# keychainlight.net
KiCad netlist of a schematic drawn in EAGLE
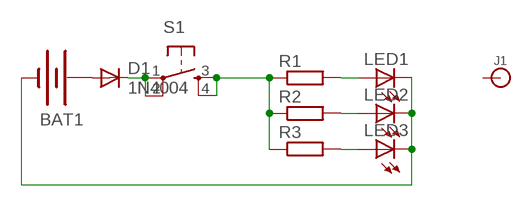
[diagram p0: schematic, sheet 1]

(export (version "E")
  (design (tool "Eeschema 10.0.6"))
  (components
    (comp (ref "BAT1")
      (value "BATTERY20PTH")
      (footprint "eagle-import:BATTCOM_20MM_PTH")
      (libsource (lib "eagle-import") (part "BATTERY20PTH"))
    )
    (comp (ref "D1")
      (value "1N4004")
      (footprint "eagle-import:DO41-10")
      (libsource (lib "eagle-import") (part "1N4004"))
    )
    (comp (ref "J1")
      (value "BANANA_CONN")
      (footprint "eagle-import:BANANA_CONN")
      (libsource (lib "eagle-import") (part "BANANA_CONN"))
    )
    (comp (ref "LED1")
      (value "LED5MM")
      (footprint "eagle-import:LED5MM")
      (libsource (lib "eagle-import") (part "LED5MM"))
    )
    (comp (ref "LED2")
      (value "LED5MM")
      (footprint "eagle-import:LED5MM")
      (libsource (lib "eagle-import") (part "LED5MM"))
    )
    (comp (ref "LED3")
      (value "LED5MM")
      (footprint "eagle-import:LED5MM")
      (libsource (lib "eagle-import") (part "LED5MM"))
    )
    (comp (ref "R1")
      (value "R-EU_0207/7")
      (footprint "eagle-import:0207_7")
      (libsource (lib "eagle-import") (part "R-EU_0207/7"))
    )
    (comp (ref "R2")
      (value "R-EU_0207/7")
      (footprint "eagle-import:0207_7")
      (libsource (lib "eagle-import") (part "R-EU_0207/7"))
    )
    (comp (ref "R3")
      (value "R-EU_0207/7")
      (footprint "eagle-import:0207_7")
      (libsource (lib "eagle-import") (part "R-EU_0207/7"))
    )
    (comp (ref "S1")
      (value "TAC_SWITCHPTH")
      (footprint "eagle-import:TACTILE-PTH")
      (libsource (lib "eagle-import") (part "TAC_SWITCHPTH"))
    )
  )
  (nets
    (net (code "1") (name "Net-(BAT1-+)") (class "Default")
      (node (ref "BAT1") (pin "1") (pinfunction "+_1") (pintype "power_in"))
      (node (ref "D1") (pin "A") (pinfunction "A_A") (pintype "passive"))
    )
    (net (code "2") (name "Net-(BAT1--)") (class "Default")
      (node (ref "BAT1") (pin "2") (pinfunction "-_2") (pintype "power_in"))
      (node (ref "LED1") (pin "K") (pinfunction "C_K") (pintype "passive"))
      (node (ref "LED2") (pin "K") (pinfunction "C_K") (pintype "passive"))
      (node (ref "LED3") (pin "K") (pinfunction "C_K") (pintype "passive"))
    )
    (net (code "3") (name "Net-(D1-PadC)") (class "Default")
      (node (ref "D1") (pin "C") (pinfunction "C_C") (pintype "passive"))
      (node (ref "S1") (pin "1") (pinfunction "1_1") (pintype "passive"))
      (node (ref "S1") (pin "2") (pinfunction "2_2") (pintype "passive"))
    )
    (net (code "4") (name "Net-(LED1-PadA)") (class "Default")
      (node (ref "LED1") (pin "A") (pinfunction "A_A") (pintype "passive"))
      (node (ref "R1") (pin "2") (pinfunction "2_2") (pintype "passive"))
    )
    (net (code "5") (name "Net-(LED2-PadA)") (class "Default")
      (node (ref "LED2") (pin "A") (pinfunction "A_A") (pintype "passive"))
      (node (ref "R2") (pin "2") (pinfunction "2_2") (pintype "passive"))
    )
    (net (code "6") (name "Net-(LED3-PadA)") (class "Default")
      (node (ref "LED3") (pin "A") (pinfunction "A_A") (pintype "passive"))
      (node (ref "R3") (pin "2") (pinfunction "2_2") (pintype "passive"))
    )
    (net (code "7") (name "Net-(R1-Pad1)") (class "Default")
      (node (ref "R1") (pin "1") (pinfunction "1_1") (pintype "passive"))
      (node (ref "R2") (pin "1") (pinfunction "1_1") (pintype "passive"))
      (node (ref "R3") (pin "1") (pinfunction "1_1") (pintype "passive"))
      (node (ref "S1") (pin "3") (pinfunction "3_3") (pintype "passive"))
      (node (ref "S1") (pin "4") (pinfunction "4_4") (pintype "passive"))
    )
    (net (code "8") (name "unconnected-(J1-1-PadP$1)") (class "Default")
      (node (ref "J1") (pin "P$1") (pinfunction "1_P$1") (pintype "passive"))
    )
  )
)
